# nomis-memory-game-v01.net
KiCad netlist of a schematic drawn in EAGLE
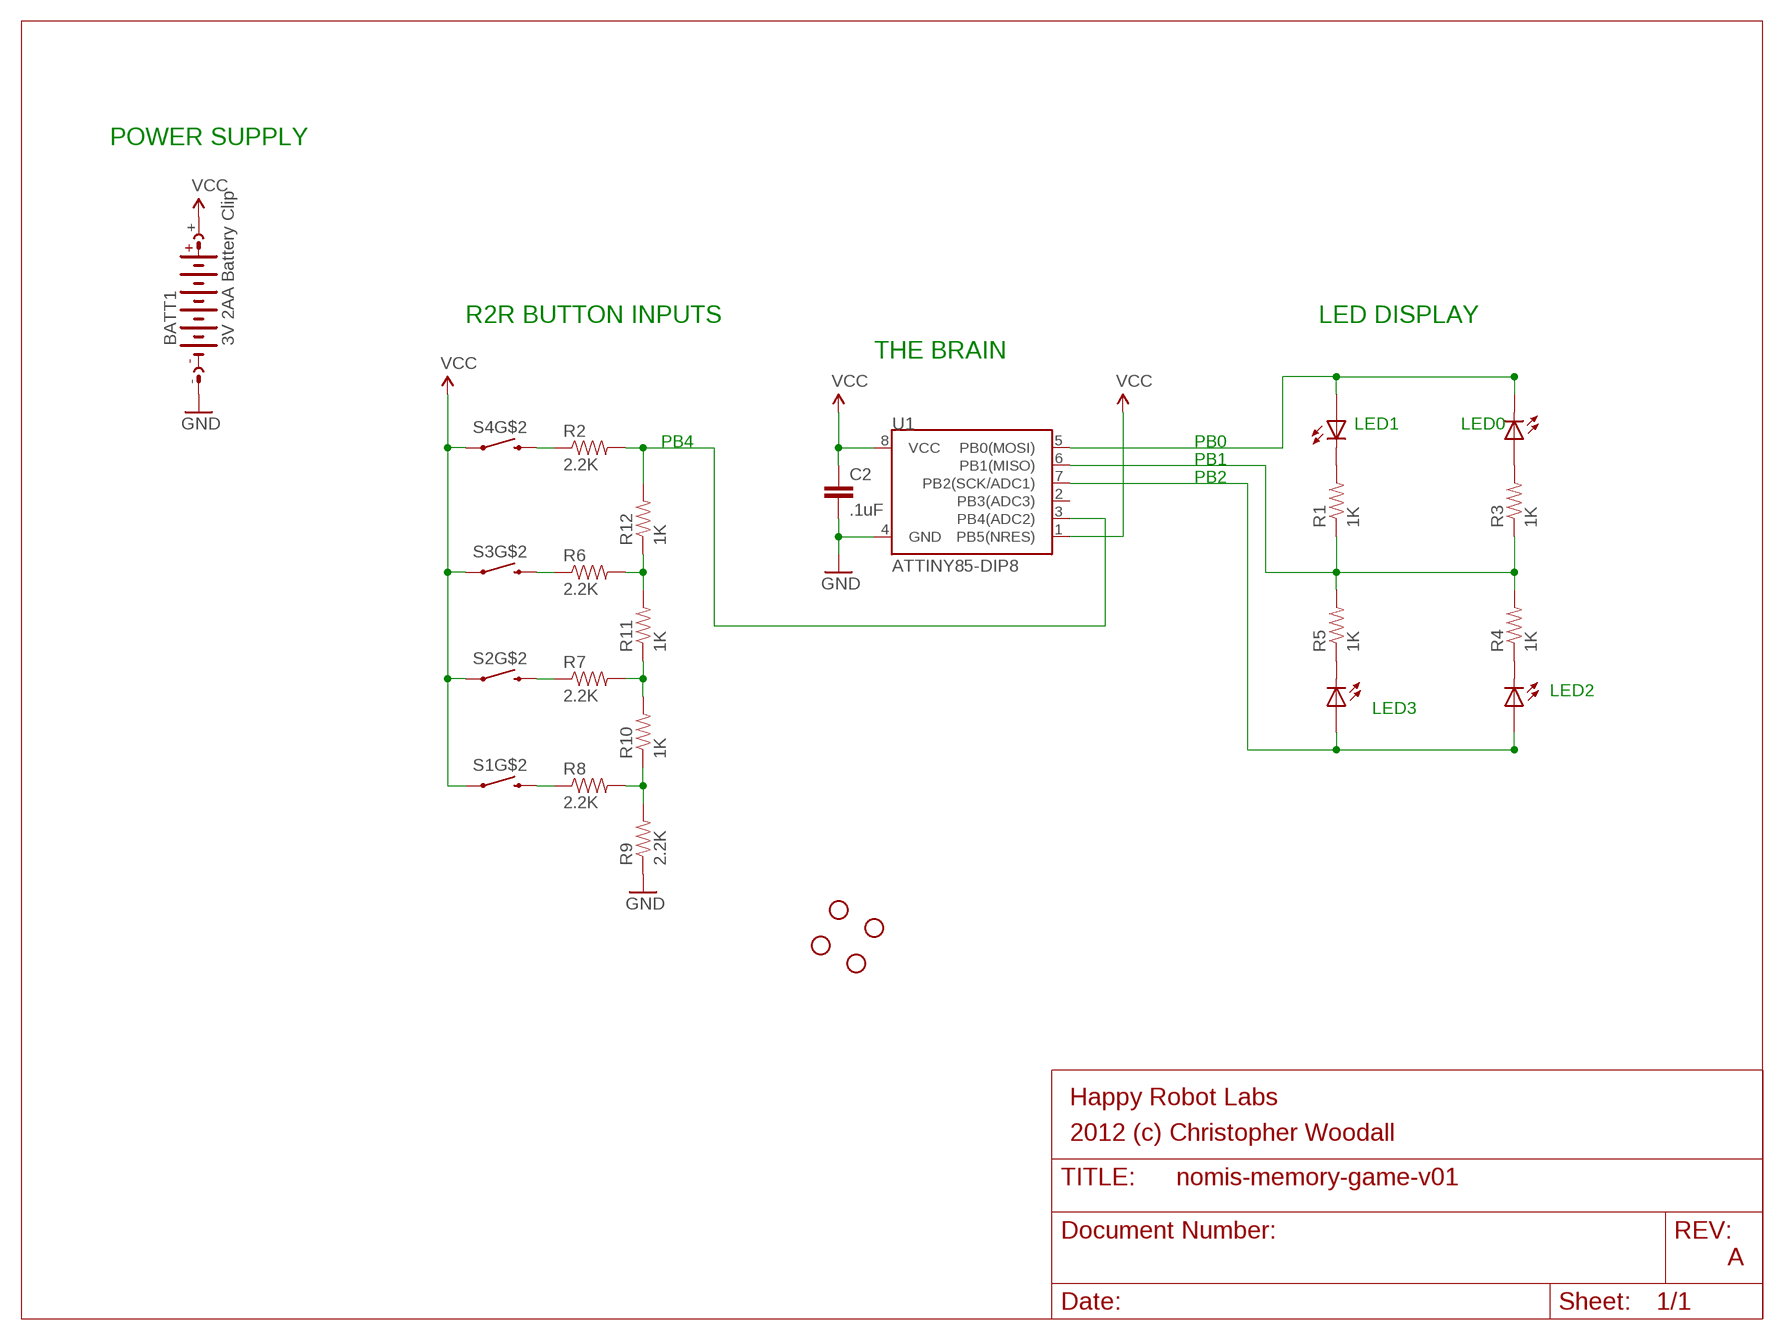
[diagram p0: schematic, sheet 1]

(export (version "E")
  (design (tool "Eeschema 10.0.6"))
  (components
    (comp (ref "BATT1")
      (value "3V 2AA Battery Clip")
      (footprint "eagle-import:AB9V")
      (libsource (lib "eagle-import") (part "AB9V"))
    )
    (comp (ref "C2")
      (value ".1uF")
      (footprint "eagle-import:CAP-PTH-SMALL")
      (libsource (lib "eagle-import") (part "CAPPTH"))
    )
    (comp (ref "JP1")
      (value "STAND-OFFTIGHT")
      (footprint "eagle-import:STAND-OFF-TIGHT")
      (libsource (lib "eagle-import") (part "STAND-OFFTIGHT"))
    )
    (comp (ref "JP2")
      (value "STAND-OFFTIGHT")
      (footprint "eagle-import:STAND-OFF-TIGHT")
      (libsource (lib "eagle-import") (part "STAND-OFFTIGHT"))
    )
    (comp (ref "JP3")
      (value "STAND-OFFTIGHT")
      (footprint "eagle-import:STAND-OFF-TIGHT")
      (libsource (lib "eagle-import") (part "STAND-OFFTIGHT"))
    )
    (comp (ref "JP4")
      (value "STAND-OFFTIGHT")
      (footprint "eagle-import:STAND-OFF-TIGHT")
      (libsource (lib "eagle-import") (part "STAND-OFFTIGHT"))
    )
    (comp (ref "R1")
      (value "1K")
      (footprint "eagle-import:AXIAL-0.4")
      (libsource (lib "eagle-import") (part "RESISTORPTH-1/4W"))
    )
    (comp (ref "R2")
      (value "2.2K")
      (footprint "eagle-import:AXIAL-0.4")
      (libsource (lib "eagle-import") (part "RESISTORPTH-1/4W"))
    )
    (comp (ref "R3")
      (value "1K")
      (footprint "eagle-import:AXIAL-0.4")
      (libsource (lib "eagle-import") (part "RESISTORPTH-1/4W"))
    )
    (comp (ref "R4")
      (value "1K")
      (footprint "eagle-import:AXIAL-0.4")
      (libsource (lib "eagle-import") (part "RESISTORPTH-1/4W"))
    )
    (comp (ref "R5")
      (value "1K")
      (footprint "eagle-import:AXIAL-0.4")
      (libsource (lib "eagle-import") (part "RESISTORPTH-1/4W"))
    )
    (comp (ref "R6")
      (value "2.2K")
      (footprint "eagle-import:AXIAL-0.4")
      (libsource (lib "eagle-import") (part "RESISTORPTH-1/4W"))
    )
    (comp (ref "R7")
      (value "2.2K")
      (footprint "eagle-import:AXIAL-0.4")
      (libsource (lib "eagle-import") (part "RESISTORPTH-1/4W"))
    )
    (comp (ref "R8")
      (value "2.2K")
      (footprint "eagle-import:AXIAL-0.4")
      (libsource (lib "eagle-import") (part "RESISTORPTH-1/4W"))
    )
    (comp (ref "R9")
      (value "2.2K")
      (footprint "eagle-import:AXIAL-0.4")
      (libsource (lib "eagle-import") (part "RESISTORPTH-1/4W"))
    )
    (comp (ref "R10")
      (value "1K")
      (footprint "eagle-import:AXIAL-0.4")
      (libsource (lib "eagle-import") (part "RESISTORPTH-1/4W"))
    )
    (comp (ref "R11")
      (value "1K")
      (footprint "eagle-import:AXIAL-0.4")
      (libsource (lib "eagle-import") (part "RESISTORPTH-1/4W"))
    )
    (comp (ref "R12")
      (value "1K")
      (footprint "eagle-import:AXIAL-0.4")
      (libsource (lib "eagle-import") (part "RESISTORPTH-1/4W"))
    )
    (comp (ref "S1")
      (value "SWITCH-MOMENTARY-LED-SPLIT")
      (footprint "eagle-import:TACTILE-PTH-LED-12MM")
      (libsource (lib "eagle-import") (part "SWITCH-MOMENTARY-LED-SPLIT"))
    )
    (comp (ref "S2")
      (value "SWITCH-MOMENTARY-LED-SPLIT")
      (footprint "eagle-import:TACTILE-PTH-LED-12MM")
      (libsource (lib "eagle-import") (part "SWITCH-MOMENTARY-LED-SPLIT"))
    )
    (comp (ref "S3")
      (value "SWITCH-MOMENTARY-LED-SPLIT")
      (footprint "eagle-import:TACTILE-PTH-LED-12MM")
      (libsource (lib "eagle-import") (part "SWITCH-MOMENTARY-LED-SPLIT"))
    )
    (comp (ref "S4")
      (value "SWITCH-MOMENTARY-LED-SPLIT")
      (footprint "eagle-import:TACTILE-PTH-LED-12MM")
      (libsource (lib "eagle-import") (part "SWITCH-MOMENTARY-LED-SPLIT"))
    )
    (comp (ref "U1")
      (value "ATTINY85-DIP8")
      (footprint "eagle-import:DIP08")
      (libsource (lib "eagle-import") (part "ATTINY45DIP8"))
    )
  )
  (nets
    (net (code "1") (name "GND") (class "Default")
      (node (ref "BATT1") (pin "-") (pinfunction "-_-") (pintype "passive"))
      (node (ref "C2") (pin "2") (pinfunction "2_2") (pintype "passive"))
      (node (ref "R9") (pin "P$1") (pinfunction "1_P$1") (pintype "passive"))
      (node (ref "U1") (pin "4") (pinfunction "GND_4") (pintype "bidirectional"))
    )
    (net (code "2") (name "Net-(R1-1)") (class "Default")
      (node (ref "R1") (pin "P$1") (pinfunction "1_P$1") (pintype "passive"))
      (node (ref "R3") (pin "P$1") (pinfunction "1_P$1") (pintype "passive"))
      (node (ref "R4") (pin "P$2") (pinfunction "2_P$2") (pintype "passive"))
      (node (ref "R5") (pin "P$2") (pinfunction "2_P$2") (pintype "passive"))
      (node (ref "U1") (pin "6") (pinfunction "PB1(MISO)_6") (pintype "bidirectional"))
    )
    (net (code "3") (name "Net-(R1-2)") (class "Default")
      (node (ref "R1") (pin "P$2") (pinfunction "2_P$2") (pintype "passive"))
      (node (ref "S2") (pin "C") (pinfunction "C_C") (pintype "passive"))
    )
    (net (code "4") (name "Net-(R2-1)") (class "Default")
      (node (ref "R2") (pin "P$1") (pinfunction "1_P$1") (pintype "passive"))
      (node (ref "S4") (pin "3") (pinfunction "2_3") (pintype "passive"))
      (node (ref "S4") (pin "4") (pinfunction "2_4") (pintype "passive"))
    )
    (net (code "5") (name "Net-(R3-2)") (class "Default")
      (node (ref "R3") (pin "P$2") (pinfunction "2_P$2") (pintype "passive"))
      (node (ref "S1") (pin "A") (pinfunction "A_A") (pintype "passive"))
    )
    (net (code "6") (name "Net-(R4-1)") (class "Default")
      (node (ref "R4") (pin "P$1") (pinfunction "1_P$1") (pintype "passive"))
      (node (ref "S3") (pin "C") (pinfunction "C_C") (pintype "passive"))
    )
    (net (code "7") (name "Net-(R5-1)") (class "Default")
      (node (ref "R5") (pin "P$1") (pinfunction "1_P$1") (pintype "passive"))
      (node (ref "S4") (pin "C") (pinfunction "C_C") (pintype "passive"))
    )
    (net (code "8") (name "Net-(R6-1)") (class "Default")
      (node (ref "R6") (pin "P$1") (pinfunction "1_P$1") (pintype "passive"))
      (node (ref "S3") (pin "3") (pinfunction "2_3") (pintype "passive"))
      (node (ref "S3") (pin "4") (pinfunction "2_4") (pintype "passive"))
    )
    (net (code "9") (name "Net-(R7-1)") (class "Default")
      (node (ref "R7") (pin "P$1") (pinfunction "1_P$1") (pintype "passive"))
      (node (ref "S2") (pin "3") (pinfunction "2_3") (pintype "passive"))
      (node (ref "S2") (pin "4") (pinfunction "2_4") (pintype "passive"))
    )
    (net (code "10") (name "Net-(R8-1)") (class "Default")
      (node (ref "R8") (pin "P$1") (pinfunction "1_P$1") (pintype "passive"))
      (node (ref "S1") (pin "3") (pinfunction "2_3") (pintype "passive"))
      (node (ref "S1") (pin "4") (pinfunction "2_4") (pintype "passive"))
    )
    (net (code "11") (name "Net-(R10-1)") (class "Default")
      (node (ref "R10") (pin "P$1") (pinfunction "1_P$1") (pintype "passive"))
      (node (ref "R8") (pin "P$2") (pinfunction "2_P$2") (pintype "passive"))
      (node (ref "R9") (pin "P$2") (pinfunction "2_P$2") (pintype "passive"))
    )
    (net (code "12") (name "Net-(R10-2)") (class "Default")
      (node (ref "R10") (pin "P$2") (pinfunction "2_P$2") (pintype "passive"))
      (node (ref "R11") (pin "P$1") (pinfunction "1_P$1") (pintype "passive"))
      (node (ref "R7") (pin "P$2") (pinfunction "2_P$2") (pintype "passive"))
    )
    (net (code "13") (name "Net-(R11-2)") (class "Default")
      (node (ref "R11") (pin "P$2") (pinfunction "2_P$2") (pintype "passive"))
      (node (ref "R12") (pin "P$1") (pinfunction "1_P$1") (pintype "passive"))
      (node (ref "R6") (pin "P$2") (pinfunction "2_P$2") (pintype "passive"))
    )
    (net (code "14") (name "Net-(R12-2)") (class "Default")
      (node (ref "R12") (pin "P$2") (pinfunction "2_P$2") (pintype "passive"))
      (node (ref "R2") (pin "P$2") (pinfunction "2_P$2") (pintype "passive"))
      (node (ref "U1") (pin "3") (pinfunction "PB4(ADC2)_3") (pintype "bidirectional"))
    )
    (net (code "15") (name "Net-(U1-PB0(MOSI))") (class "Default")
      (node (ref "S1") (pin "C") (pinfunction "C_C") (pintype "passive"))
      (node (ref "S2") (pin "A") (pinfunction "A_A") (pintype "passive"))
      (node (ref "U1") (pin "5") (pinfunction "PB0(MOSI)_5") (pintype "bidirectional"))
    )
    (net (code "16") (name "Net-(U1-PB2(SCK{slash}ADC1))") (class "Default")
      (node (ref "S3") (pin "A") (pinfunction "A_A") (pintype "passive"))
      (node (ref "S4") (pin "A") (pinfunction "A_A") (pintype "passive"))
      (node (ref "U1") (pin "7") (pinfunction "PB2(SCK/ADC1)_7") (pintype "bidirectional"))
    )
    (net (code "17") (name "VCC") (class "Default")
      (node (ref "BATT1") (pin "+") (pinfunction "+_+") (pintype "passive"))
      (node (ref "C2") (pin "1") (pinfunction "1_1") (pintype "passive"))
      (node (ref "S1") (pin "1") (pinfunction "1_1") (pintype "passive"))
      (node (ref "S1") (pin "2") (pinfunction "1_2") (pintype "passive"))
      (node (ref "S2") (pin "1") (pinfunction "1_1") (pintype "passive"))
      (node (ref "S2") (pin "2") (pinfunction "1_2") (pintype "passive"))
      (node (ref "S3") (pin "1") (pinfunction "1_1") (pintype "passive"))
      (node (ref "S3") (pin "2") (pinfunction "1_2") (pintype "passive"))
      (node (ref "S4") (pin "1") (pinfunction "1_1") (pintype "passive"))
      (node (ref "S4") (pin "2") (pinfunction "1_2") (pintype "passive"))
      (node (ref "U1") (pin "1") (pinfunction "PB5(NRES)_1") (pintype "bidirectional"))
      (node (ref "U1") (pin "8") (pinfunction "VCC_8") (pintype "bidirectional"))
    )
    (net (code "18") (name "unconnected-(U1-PB3(ADC3)-Pad2)") (class "Default")
      (node (ref "U1") (pin "2") (pinfunction "PB3(ADC3)_2") (pintype "bidirectional"))
    )
  )
)
